# CW340_PSU_VCCIO.net
KiCad netlist of a schematic drawn in Altium Designer
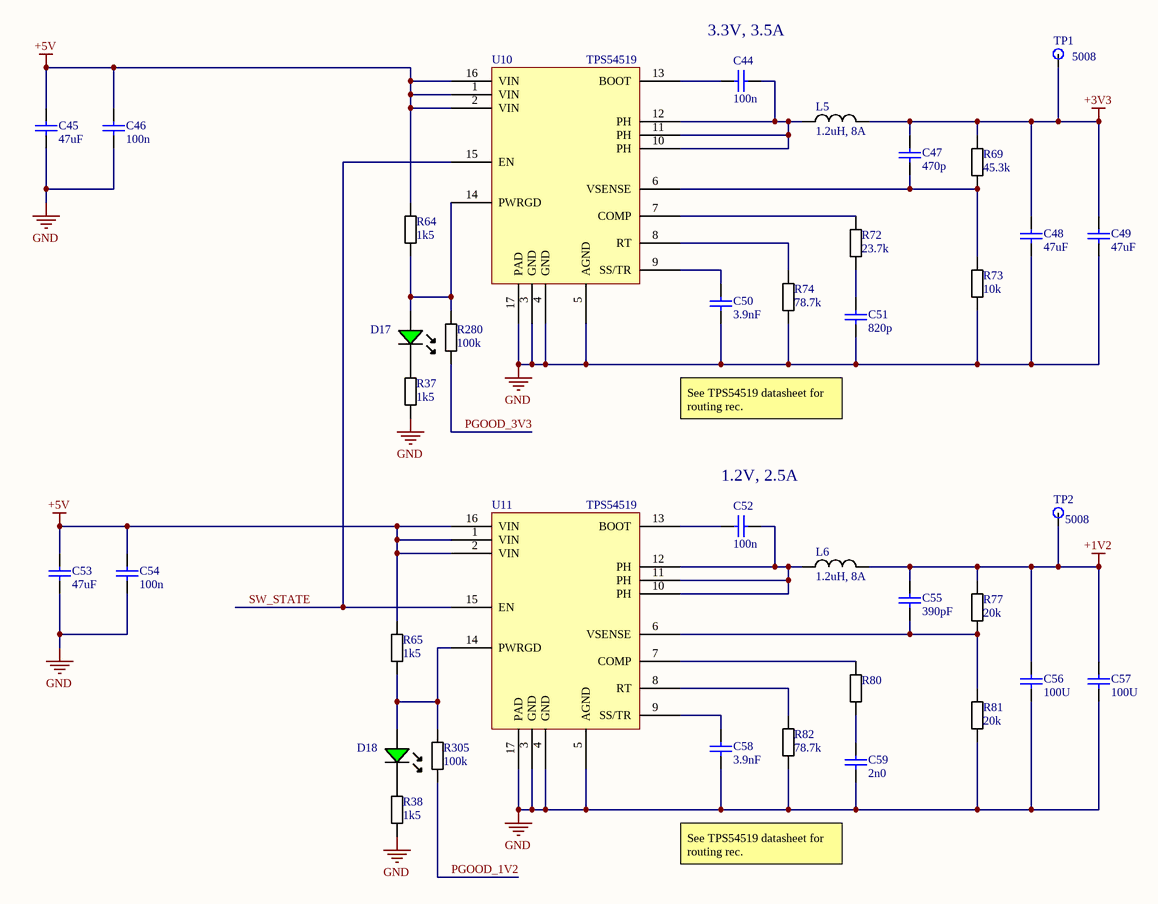
[diagram p0: CW340_PSU_VCCIO.SchDoc]

(export (version "E")
  (design (tool "Eeschema 10.0.6"))
  (components
    (comp (ref "C44")
      (value "100n")
      (footprint "CAPC0603_M")
      (description "100n, 0603")
      (fields (field (name "PART NUMBER") "CCHIP-100n-0603"))
      (libsource (lib "NewAE_AltiumLib") (part "CAP"))
    )
    (comp (ref "C45")
      (value "47uF")
      (footprint "CAPC3225X20N")
      (description "47u, 10V, 1210, Ceramic")
      (fields (field (name "PART NUMBER") "CCHIP-47u-1210") (field (name "TOLERANCE") "20%"))
      (libsource (lib "NewAE_AltiumLib") (part "CAP"))
    )
    (comp (ref "C46")
      (value "100n")
      (footprint "CAPC0603_M")
      (description "100n, 0603")
      (fields (field (name "PART NUMBER") "CCHIP-100n-0603"))
      (libsource (lib "NewAE_AltiumLib") (part "CAP"))
    )
    (comp (ref "C47")
      (value "470p")
      (footprint "RESC1608X55N")
      (description "CAP CER 470PF 100V X7R 0603")
      (fields (field (name "PART NUMBER") "CCHIP-470P-0603-100V") (field (name "TOLERANCE") "±10%"))
      (libsource (lib "NewAE_AltiumLib") (part "CAP"))
    )
    (comp (ref "C48")
      (value "47uF")
      (footprint "CAPC3225X20N")
      (description "47u, 10V, 1210, Ceramic")
      (fields (field (name "PART NUMBER") "CCHIP-47u-1210") (field (name "TOLERANCE") "20%"))
      (libsource (lib "NewAE_AltiumLib") (part "CAP"))
    )
    (comp (ref "C49")
      (value "47uF")
      (footprint "CAPC3225X20N")
      (description "47u, 10V, 1210, Ceramic")
      (fields (field (name "PART NUMBER") "CCHIP-47u-1210") (field (name "TOLERANCE") "20%"))
      (libsource (lib "NewAE_AltiumLib") (part "CAP"))
    )
    (comp (ref "C50")
      (value "3.9nF")
      (footprint "CAPC0603_M")
      (description "3n9, 0603")
      (fields (field (name "PART NUMBER") "CCHIP-3n9-0603") (field (name "TOLERANCE") "1%"))
      (libsource (lib "NewAE_AltiumLib") (part "CAP"))
    )
    (comp (ref "C51")
      (value "820p")
      (footprint "RESC1608X55N")
      (description "CAP CER 820PF 100V X7R 0603")
      (fields (field (name "PART NUMBER") "CCHIP-820P-0603-100V") (field (name "TOLERANCE") "±10%"))
      (libsource (lib "NewAE_AltiumLib") (part "CAP"))
    )
    (comp (ref "C52")
      (value "100n")
      (footprint "CAPC0603_M")
      (description "100n, 0603")
      (fields (field (name "PART NUMBER") "CCHIP-100n-0603"))
      (libsource (lib "NewAE_AltiumLib") (part "CAP"))
    )
    (comp (ref "C53")
      (value "47uF")
      (footprint "CAPC3225X20N")
      (description "47u, 10V, 1210, Ceramic")
      (fields (field (name "PART NUMBER") "CCHIP-47u-1210") (field (name "TOLERANCE") "20%"))
      (libsource (lib "NewAE_AltiumLib") (part "CAP"))
    )
    (comp (ref "C54")
      (value "100n")
      (footprint "CAPC0603_M")
      (description "100n, 0603")
      (fields (field (name "PART NUMBER") "CCHIP-100n-0603"))
      (libsource (lib "NewAE_AltiumLib") (part "CAP"))
    )
    (comp (ref "C55")
      (value "390pF")
      (footprint "CAPC0603_M")
      (description "390p, 0603, C0G/NP0")
      (fields (field (name "PART NUMBER") "CCHIP-390p-0603-C0G") (field (name "TOLERANCE") "5%"))
      (libsource (lib "NewAE_AltiumLib") (part "CAP"))
    )
    (comp (ref "C56")
      (value "100U")
      (footprint "CAPC1206_M")
      (description "CAP CER 100UF 6.3V X5R 1206")
      (fields (field (name "PART NUMBER") "CCHIP-100u-1206-6.3v"))
      (libsource (lib "NewAE_AltiumLib") (part "CAP"))
    )
    (comp (ref "C57")
      (value "100U")
      (footprint "CAPC1206_M")
      (description "CAP CER 100UF 6.3V X5R 1206")
      (fields (field (name "PART NUMBER") "CCHIP-100u-1206-6.3v"))
      (libsource (lib "NewAE_AltiumLib") (part "CAP"))
    )
    (comp (ref "C58")
      (value "3.9nF")
      (footprint "CAPC0603_M")
      (description "3n9, 0603")
      (fields (field (name "PART NUMBER") "CCHIP-3n9-0603") (field (name "TOLERANCE") "1%"))
      (libsource (lib "NewAE_AltiumLib") (part "CAP"))
    )
    (comp (ref "C59")
      (value "2n0")
      (footprint "CAPC0603_M")
      (description "2n, 0603, C0G/NP0")
      (fields (field (name "PART NUMBER") "CCHIP-2n-0603-C0G") (field (name "TOLERANCE") "1%"))
      (libsource (lib "NewAE_AltiumLib") (part "CAP"))
    )
    (comp (ref "D17")
      (value "LED, 0603, Green")
      (footprint "LED-0603-GREEN")
      (description "Chip LED, Green")
      (fields (field (name "PART NUMBER") "LEDCHIP_0603_GREEN"))
      (libsource (lib "NewAE_AltiumLib") (part "LED_GREEN"))
    )
    (comp (ref "D18")
      (value "LED, 0603, Green")
      (footprint "LED-0603-GREEN")
      (description "Chip LED, Green")
      (fields (field (name "PART NUMBER") "LEDCHIP_0603_GREEN"))
      (libsource (lib "NewAE_AltiumLib") (part "LED_GREEN"))
    )
    (comp (ref "L5")
      (value "1.2uH, 8A")
      (footprint "XAL5030-122")
      (description "1.2uH, 8A RMS, 12A SAT")
      (fields (field (name "PART NUMBER") "XAL5030-122"))
      (libsource (lib "NewAE_AltiumLib") (part "IND"))
    )
    (comp (ref "L6")
      (value "1.2uH, 8A")
      (footprint "XAL5030-122")
      (description "1.2uH, 8A RMS, 12A SAT")
      (fields (field (name "PART NUMBER") "XAL5030-122"))
      (libsource (lib "NewAE_AltiumLib") (part "IND"))
    )
    (comp (ref "R37")
      (value "1k5")
      (footprint "RESC1608X55N")
      (description "1k5 res, 0603, 1%, 1/10W")
      (fields (field (name "PART NUMBER") "RCHIP-1K5-0603") (field (name "TOLERANCE") "1%"))
      (libsource (lib "NewAE_AltiumLib") (part "RES-EU"))
    )
    (comp (ref "R38")
      (value "1k5")
      (footprint "RESC1608X55N")
      (description "1k5 res, 0603, 1%, 1/10W")
      (fields (field (name "PART NUMBER") "RCHIP-1K5-0603") (field (name "TOLERANCE") "1%"))
      (libsource (lib "NewAE_AltiumLib") (part "RES-EU"))
    )
    (comp (ref "R64")
      (value "1k5")
      (footprint "RESC1608X55N")
      (description "1k5 res, 0603, 1%, 1/10W")
      (fields (field (name "PART NUMBER") "RCHIP-1K5-0603") (field (name "TOLERANCE") "1%"))
      (libsource (lib "NewAE_AltiumLib") (part "RES-EU"))
    )
    (comp (ref "R65")
      (value "1k5")
      (footprint "RESC1608X55N")
      (description "1k5 res, 0603, 1%, 1/10W")
      (fields (field (name "PART NUMBER") "RCHIP-1K5-0603") (field (name "TOLERANCE") "1%"))
      (libsource (lib "NewAE_AltiumLib") (part "RES-EU"))
    )
    (comp (ref "R69")
      (value "45.3k")
      (footprint "RESC1608X55N")
      (description "45k3 res, 0603, 1%, 1/10W")
      (fields (field (name "PART NUMBER") "RCHIP-45K3-0603") (field (name "TOLERANCE") "1%"))
      (libsource (lib "NewAE_AltiumLib") (part "RES-EU"))
    )
    (comp (ref "R72")
      (value "23.7k")
      (footprint "RESC1608X55N")
      (description "23k7 res, 0603, 1%, 1/10W")
      (fields (field (name "PART NUMBER") "RCHIP-23k7-0603") (field (name "TOLERANCE") "1%"))
      (libsource (lib "NewAE_AltiumLib") (part "RES-EU"))
    )
    (comp (ref "R73")
      (value "10k")
      (footprint "RESC1608X55N")
      (description "10k res, 0603, 1%, 1/10W")
      (fields (field (name "PART NUMBER") "RCHIP-10K-0603") (field (name "TOLERANCE") "1%"))
      (libsource (lib "NewAE_AltiumLib") (part "RES-EU"))
    )
    (comp (ref "R74")
      (value "78.7k")
      (footprint "RESC1608X55N")
      (description "78k7 res, 0603, 1%, 1/10W")
      (fields (field (name "PART NUMBER") "RCHIP-78k7-0603") (field (name "TOLERANCE") "1%"))
      (libsource (lib "NewAE_AltiumLib") (part "RES-EU"))
    )
    (comp (ref "R77")
      (value "20k")
      (footprint "RESC1608X55N")
      (description "20k res, 0603, 1%, 1/10W")
      (fields (field (name "PART NUMBER") "RCHIP-20K-0603") (field (name "TOLERANCE") "1%"))
      (libsource (lib "NewAE_AltiumLib") (part "RES-EU"))
    )
    (comp (ref "R80")
      (value "~")
      (footprint "RESC1608X55N")
      (description "12k1 res, 0603, 1%, 1/10W")
      (fields (field (name "PART NUMBER") "RCHIP-12k1-0603") (field (name "TOLERANCE") "1%"))
      (libsource (lib "NewAE_AltiumLib") (part "RES-EU"))
    )
    (comp (ref "R81")
      (value "20k")
      (footprint "RESC1608X55N")
      (description "20k res, 0603, 1%, 1/10W")
      (fields (field (name "PART NUMBER") "RCHIP-20K-0603") (field (name "TOLERANCE") "1%"))
      (libsource (lib "NewAE_AltiumLib") (part "RES-EU"))
    )
    (comp (ref "R82")
      (value "78.7k")
      (footprint "RESC1608X55N")
      (description "78k7 res, 0603, 1%, 1/10W")
      (fields (field (name "PART NUMBER") "RCHIP-78k7-0603") (field (name "TOLERANCE") "1%"))
      (libsource (lib "NewAE_AltiumLib") (part "RES-EU"))
    )
    (comp (ref "R280")
      (value "100k")
      (footprint "RESC1608X55N")
      (description "100k res, 0603, 1%, 1/10W")
      (fields (field (name "PART NUMBER") "RCHIP-100K-0603") (field (name "TOLERANCE") "1%"))
      (libsource (lib "NewAE_AltiumLib") (part "RES-EU"))
    )
    (comp (ref "R305")
      (value "100k")
      (footprint "RESC1608X55N")
      (description "100k res, 0603, 1%, 1/10W")
      (fields (field (name "PART NUMBER") "RCHIP-100K-0603") (field (name "TOLERANCE") "1%"))
      (libsource (lib "NewAE_AltiumLib") (part "RES-EU"))
    )
    (comp (ref "TP1")
      (value "5008")
      (footprint "KEYSTONE5008")
      (description "TEST POINT PC COMPACT .063\"D ORG")
      (fields (field (name "PART NUMBER") "KEYSTONE_5008"))
      (libsource (lib "NewAE_AltiumLib") (part "KEYSTONE_5008"))
    )
    (comp (ref "TP2")
      (value "5008")
      (footprint "KEYSTONE5008")
      (description "TEST POINT PC COMPACT .063\"D ORG")
      (fields (field (name "PART NUMBER") "KEYSTONE_5008"))
      (libsource (lib "NewAE_AltiumLib") (part "KEYSTONE_5008"))
    )
    (comp (ref "U10")
      (value "TPS54519")
      (footprint "QFN50P300X300X80_HS-17N")
      (description "6V Input, 5A, SMPS")
      (libsource (lib "NewAE_AltiumLib") (part "TPS54519"))
    )
    (comp (ref "U11")
      (value "TPS54519")
      (footprint "QFN50P300X300X80_HS-17N")
      (description "6V Input, 5A, SMPS")
      (libsource (lib "NewAE_AltiumLib") (part "TPS54519"))
    )
  )
  (nets
    (net (code "1") (name "+1V2") (class "Default")
      (node (ref "C55") (pin "1") (pinfunction "1_1") (pintype "passive"))
      (node (ref "C56") (pin "1") (pinfunction "1_1") (pintype "passive"))
      (node (ref "C57") (pin "1") (pinfunction "1_1") (pintype "passive"))
      (node (ref "L6") (pin "2") (pinfunction "2_2") (pintype "passive"))
      (node (ref "R77") (pin "1") (pinfunction "1_1") (pintype "passive"))
      (node (ref "TP2") (pin "1") (pinfunction "1_1") (pintype "passive"))
    )
    (net (code "2") (name "+3V3") (class "Default")
      (node (ref "C47") (pin "2") (pinfunction "2_2") (pintype "passive"))
      (node (ref "C48") (pin "1") (pinfunction "1_1") (pintype "passive"))
      (node (ref "C49") (pin "1") (pinfunction "1_1") (pintype "passive"))
      (node (ref "L5") (pin "2") (pinfunction "2_2") (pintype "passive"))
      (node (ref "R69") (pin "1") (pinfunction "1_1") (pintype "passive"))
      (node (ref "TP1") (pin "1") (pinfunction "1_1") (pintype "passive"))
    )
    (net (code "3") (name "+5V") (class "Default")
      (node (ref "C45") (pin "1") (pinfunction "1_1") (pintype "passive"))
      (node (ref "C46") (pin "2") (pinfunction "2_2") (pintype "passive"))
      (node (ref "C53") (pin "1") (pinfunction "1_1") (pintype "passive"))
      (node (ref "C54") (pin "2") (pinfunction "2_2") (pintype "passive"))
      (node (ref "R64") (pin "1") (pinfunction "1_1") (pintype "passive"))
      (node (ref "R65") (pin "1") (pinfunction "1_1") (pintype "passive"))
      (node (ref "U10") (pin "1") (pinfunction "VIN_1") (pintype "passive"))
      (node (ref "U10") (pin "16") (pinfunction "VIN_16") (pintype "passive"))
      (node (ref "U10") (pin "2") (pinfunction "VIN_2") (pintype "passive"))
      (node (ref "U11") (pin "1") (pinfunction "VIN_1") (pintype "passive"))
      (node (ref "U11") (pin "16") (pinfunction "VIN_16") (pintype "passive"))
      (node (ref "U11") (pin "2") (pinfunction "VIN_2") (pintype "passive"))
    )
    (net (code "4") (name "/PGOOD_1V2") (class "Default")
      (node (ref "R305") (pin "2") (pinfunction "2_2") (pintype "passive"))
    )
    (net (code "5") (name "/PGOOD_3V3") (class "Default")
      (node (ref "R280") (pin "2") (pinfunction "2_2") (pintype "passive"))
    )
    (net (code "6") (name "/SW_STATE") (class "Default")
      (node (ref "U10") (pin "15") (pinfunction "EN_15") (pintype "passive"))
      (node (ref "U11") (pin "15") (pinfunction "EN_15") (pintype "passive"))
    )
    (net (code "7") (name "GND") (class "Default")
      (node (ref "C45") (pin "2") (pinfunction "2_2") (pintype "passive"))
      (node (ref "C46") (pin "1") (pinfunction "1_1") (pintype "passive"))
      (node (ref "C48") (pin "2") (pinfunction "2_2") (pintype "passive"))
      (node (ref "C49") (pin "2") (pinfunction "2_2") (pintype "passive"))
      (node (ref "C50") (pin "2") (pinfunction "2_2") (pintype "passive"))
      (node (ref "C51") (pin "2") (pinfunction "2_2") (pintype "passive"))
      (node (ref "C53") (pin "2") (pinfunction "2_2") (pintype "passive"))
      (node (ref "C54") (pin "1") (pinfunction "1_1") (pintype "passive"))
      (node (ref "C56") (pin "2") (pinfunction "2_2") (pintype "passive"))
      (node (ref "C57") (pin "2") (pinfunction "2_2") (pintype "passive"))
      (node (ref "C58") (pin "2") (pinfunction "2_2") (pintype "passive"))
      (node (ref "C59") (pin "2") (pinfunction "2_2") (pintype "passive"))
      (node (ref "R37") (pin "2") (pinfunction "2_2") (pintype "passive"))
      (node (ref "R38") (pin "2") (pinfunction "2_2") (pintype "passive"))
      (node (ref "R73") (pin "2") (pinfunction "2_2") (pintype "passive"))
      (node (ref "R74") (pin "2") (pinfunction "2_2") (pintype "passive"))
      (node (ref "R81") (pin "2") (pinfunction "2_2") (pintype "passive"))
      (node (ref "R82") (pin "2") (pinfunction "2_2") (pintype "passive"))
      (node (ref "U10") (pin "17") (pinfunction "PAD_17") (pintype "passive"))
      (node (ref "U10") (pin "3") (pinfunction "GND_3") (pintype "passive"))
      (node (ref "U10") (pin "4") (pinfunction "GND_4") (pintype "passive"))
      (node (ref "U10") (pin "5") (pinfunction "AGND_5") (pintype "passive"))
      (node (ref "U11") (pin "17") (pinfunction "PAD_17") (pintype "passive"))
      (node (ref "U11") (pin "3") (pinfunction "GND_3") (pintype "passive"))
      (node (ref "U11") (pin "4") (pinfunction "GND_4") (pintype "passive"))
      (node (ref "U11") (pin "5") (pinfunction "AGND_5") (pintype "passive"))
    )
    (net (code "8") (name "Net-(C44-Pad2)") (class "Default")
      (node (ref "C44") (pin "2") (pinfunction "2_2") (pintype "passive"))
      (node (ref "L5") (pin "1") (pinfunction "1_1") (pintype "passive"))
      (node (ref "U10") (pin "10") (pinfunction "PH_10") (pintype "passive"))
      (node (ref "U10") (pin "11") (pinfunction "PH_11") (pintype "passive"))
      (node (ref "U10") (pin "12") (pinfunction "PH_12") (pintype "passive"))
    )
    (net (code "9") (name "Net-(C51-Pad1)") (class "Default")
      (node (ref "C51") (pin "1") (pinfunction "1_1") (pintype "passive"))
      (node (ref "R72") (pin "2") (pinfunction "2_2") (pintype "passive"))
    )
    (net (code "10") (name "Net-(C52-Pad2)") (class "Default")
      (node (ref "C52") (pin "2") (pinfunction "2_2") (pintype "passive"))
      (node (ref "L6") (pin "1") (pinfunction "1_1") (pintype "passive"))
      (node (ref "U11") (pin "10") (pinfunction "PH_10") (pintype "passive"))
      (node (ref "U11") (pin "11") (pinfunction "PH_11") (pintype "passive"))
      (node (ref "U11") (pin "12") (pinfunction "PH_12") (pintype "passive"))
    )
    (net (code "11") (name "Net-(C59-Pad1)") (class "Default")
      (node (ref "C59") (pin "1") (pinfunction "1_1") (pintype "passive"))
      (node (ref "R80") (pin "2") (pinfunction "2_2") (pintype "passive"))
    )
    (net (code "12") (name "Net-(D17-PadK)") (class "Default")
      (node (ref "D17") (pin "K") (pinfunction "K_K") (pintype "passive"))
      (node (ref "R37") (pin "1") (pinfunction "1_1") (pintype "passive"))
    )
    (net (code "13") (name "Net-(D18-PadK)") (class "Default")
      (node (ref "D18") (pin "K") (pinfunction "K_K") (pintype "passive"))
      (node (ref "R38") (pin "1") (pinfunction "1_1") (pintype "passive"))
    )
    (net (code "14") (name "Net-(U10-BOOT)") (class "Default")
      (node (ref "C44") (pin "1") (pinfunction "1_1") (pintype "passive"))
      (node (ref "U10") (pin "13") (pinfunction "BOOT_13") (pintype "passive"))
    )
    (net (code "15") (name "Net-(U10-COMP)") (class "Default")
      (node (ref "R72") (pin "1") (pinfunction "1_1") (pintype "passive"))
      (node (ref "U10") (pin "7") (pinfunction "COMP_7") (pintype "passive"))
    )
    (net (code "16") (name "Net-(U10-PWRGD)") (class "Default")
      (node (ref "D17") (pin "A") (pinfunction "A_A") (pintype "passive"))
      (node (ref "R280") (pin "1") (pinfunction "1_1") (pintype "passive"))
      (node (ref "R64") (pin "2") (pinfunction "2_2") (pintype "passive"))
      (node (ref "U10") (pin "14") (pinfunction "PWRGD_14") (pintype "passive"))
    )
    (net (code "17") (name "Net-(U10-RT)") (class "Default")
      (node (ref "R74") (pin "1") (pinfunction "1_1") (pintype "passive"))
      (node (ref "U10") (pin "8") (pinfunction "RT_8") (pintype "passive"))
    )
    (net (code "18") (name "Net-(U10-SS{slash}TR)") (class "Default")
      (node (ref "C50") (pin "1") (pinfunction "1_1") (pintype "passive"))
      (node (ref "U10") (pin "9") (pinfunction "SS/TR_9") (pintype "passive"))
    )
    (net (code "19") (name "Net-(U10-VSENSE)") (class "Default")
      (node (ref "C47") (pin "1") (pinfunction "1_1") (pintype "passive"))
      (node (ref "R69") (pin "2") (pinfunction "2_2") (pintype "passive"))
      (node (ref "R73") (pin "1") (pinfunction "1_1") (pintype "passive"))
      (node (ref "U10") (pin "6") (pinfunction "VSENSE_6") (pintype "passive"))
    )
    (net (code "20") (name "Net-(U11-BOOT)") (class "Default")
      (node (ref "C52") (pin "1") (pinfunction "1_1") (pintype "passive"))
      (node (ref "U11") (pin "13") (pinfunction "BOOT_13") (pintype "passive"))
    )
    (net (code "21") (name "Net-(U11-COMP)") (class "Default")
      (node (ref "R80") (pin "1") (pinfunction "1_1") (pintype "passive"))
      (node (ref "U11") (pin "7") (pinfunction "COMP_7") (pintype "passive"))
    )
    (net (code "22") (name "Net-(U11-PWRGD)") (class "Default")
      (node (ref "D18") (pin "A") (pinfunction "A_A") (pintype "passive"))
      (node (ref "R305") (pin "1") (pinfunction "1_1") (pintype "passive"))
      (node (ref "R65") (pin "2") (pinfunction "2_2") (pintype "passive"))
      (node (ref "U11") (pin "14") (pinfunction "PWRGD_14") (pintype "passive"))
    )
    (net (code "23") (name "Net-(U11-RT)") (class "Default")
      (node (ref "R82") (pin "1") (pinfunction "1_1") (pintype "passive"))
      (node (ref "U11") (pin "8") (pinfunction "RT_8") (pintype "passive"))
    )
    (net (code "24") (name "Net-(U11-SS{slash}TR)") (class "Default")
      (node (ref "C58") (pin "1") (pinfunction "1_1") (pintype "passive"))
      (node (ref "U11") (pin "9") (pinfunction "SS/TR_9") (pintype "passive"))
    )
    (net (code "25") (name "Net-(U11-VSENSE)") (class "Default")
      (node (ref "C55") (pin "2") (pinfunction "2_2") (pintype "passive"))
      (node (ref "R77") (pin "2") (pinfunction "2_2") (pintype "passive"))
      (node (ref "R81") (pin "1") (pinfunction "1_1") (pintype "passive"))
      (node (ref "U11") (pin "6") (pinfunction "VSENSE_6") (pintype "passive"))
    )
  )
)
